# Mainboard_MCU_Breakout.net
KiCad netlist of a schematic drawn in Altium Designer
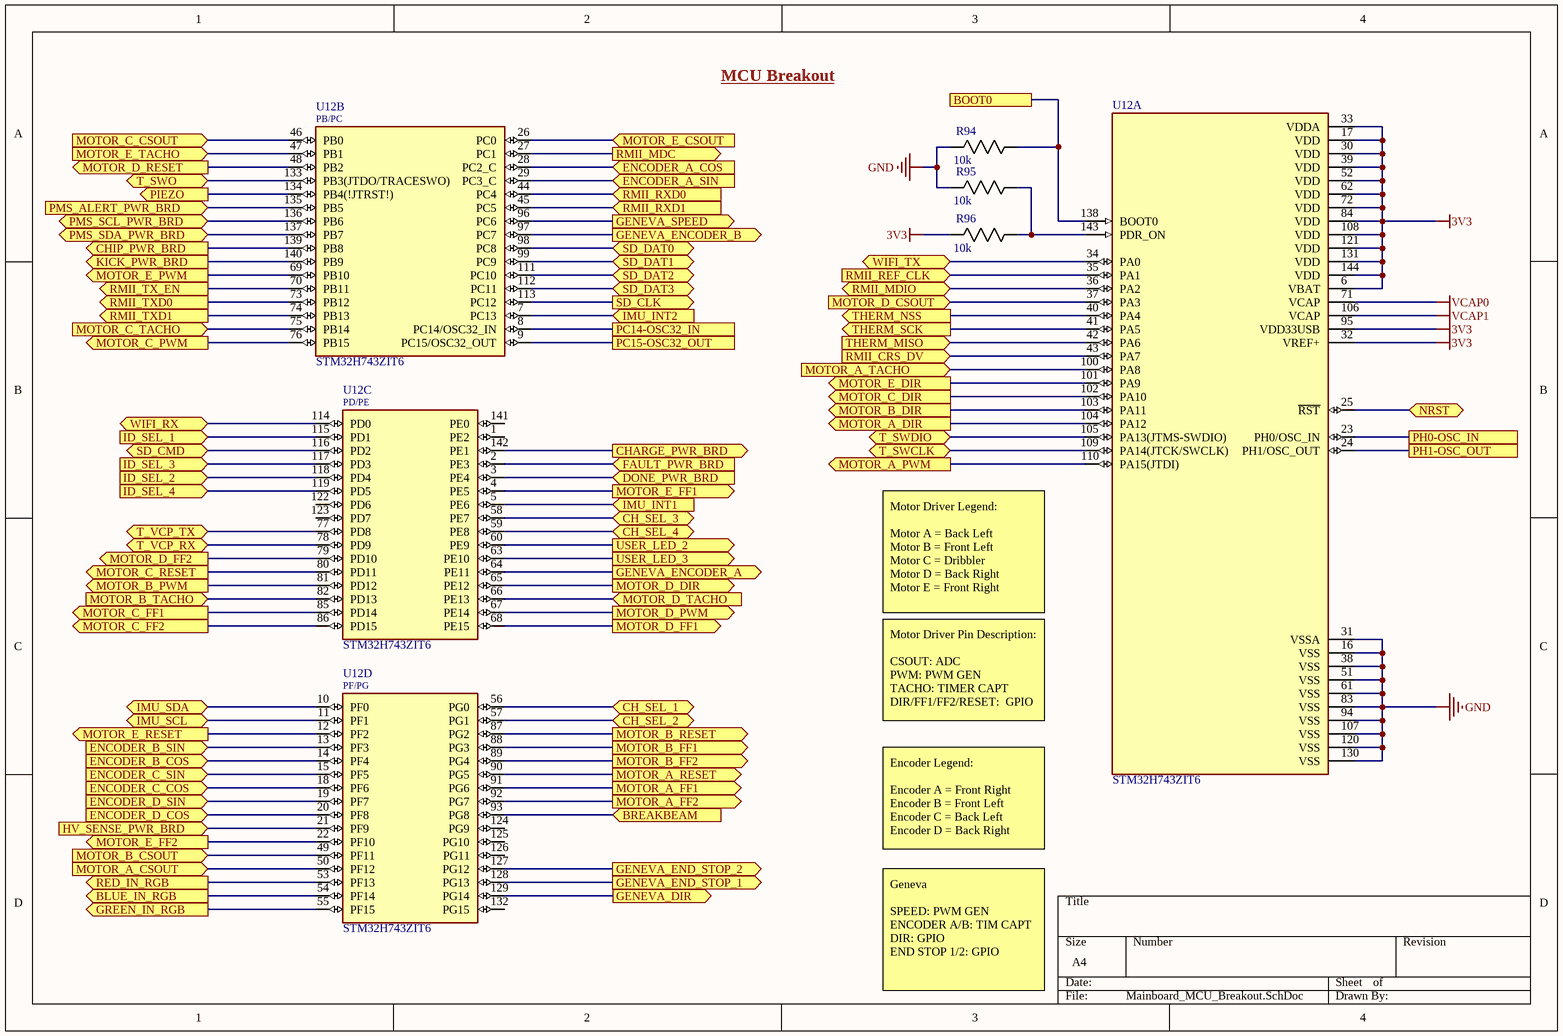
[diagram p0: Mainboard_MCU_Breakout.SchDoc]

(export (version "E")
  (design (tool "Eeschema 10.0.6"))
  (components
    (comp (ref "R94")
      (value "10k")
      (footprint "0805")
      (description "RES SMD 10K OHM 1% 1/8W 0805")
      (fields (field (name "TOLERANCE") "1%"))
      (libsource (lib "") (part "RES 10k 1/8W - 1%_1"))
    )
    (comp (ref "R95")
      (value "10k")
      (footprint "0805")
      (description "RES SMD 10K OHM 1% 1/8W 0805")
      (fields (field (name "TOLERANCE") "1%"))
      (libsource (lib "AltiumLibraries") (part "RES 10k 1/8W - 1%"))
    )
    (comp (ref "R96")
      (value "10k")
      (footprint "0805")
      (description "RES SMD 10K OHM 1% 1/8W 0805")
      (fields (field (name "TOLERANCE") "1%"))
      (libsource (lib "AltiumLibraries") (part "RES 10k 1/8W - 1%"))
    )
    (comp (ref "U12")
      (value "STM32H743ZIT6")
      (footprint "QFP50P2200X2200X160-144N")
      (description "ARM® Cortex®-M7 STM32H7 Microcontroller IC 32-Bit 480MHz 2MB (2M x 8) FLASH 144-LQFP (20x20)")
      (fields (field (name "MF") "STMicroelectronics"))
      (libsource (lib "AltiumLibraries") (part "STM32H743ZIT6"))
    )
  )
  (nets
    (net (code "1") (name "/BLUE_IN_RGB") (class "Default")
      (node (ref "U12") (pin "54") (pinfunction "PF14_54") (pintype "bidirectional"))
    )
    (net (code "2") (name "/BOOT0") (class "Default")
      (node (ref "R94") (pin "1") (pinfunction "R1_1") (pintype "passive"))
      (node (ref "U12") (pin "138") (pinfunction "BOOT0_138") (pintype "input"))
    )
    (net (code "3") (name "/BREAKBEAM") (class "Default")
      (node (ref "U12") (pin "93") (pinfunction "PG8_93") (pintype "bidirectional"))
    )
    (net (code "4") (name "/CHARGE_PWR_BRD") (class "Default")
      (node (ref "U12") (pin "142") (pinfunction "PE1_142") (pintype "bidirectional"))
    )
    (net (code "5") (name "/CHIP_PWR_BRD") (class "Default")
      (node (ref "U12") (pin "139") (pinfunction "PB8_139") (pintype "bidirectional"))
    )
    (net (code "6") (name "/CH_SEL_1") (class "Default")
      (node (ref "U12") (pin "56") (pinfunction "PG0_56") (pintype "bidirectional"))
    )
    (net (code "7") (name "/CH_SEL_2") (class "Default")
      (node (ref "U12") (pin "57") (pinfunction "PG1_57") (pintype "bidirectional"))
    )
    (net (code "8") (name "/CH_SEL_3") (class "Default")
      (node (ref "U12") (pin "58") (pinfunction "PE7_58") (pintype "bidirectional"))
    )
    (net (code "9") (name "/CH_SEL_4") (class "Default")
      (node (ref "U12") (pin "59") (pinfunction "PE8_59") (pintype "bidirectional"))
    )
    (net (code "10") (name "/DONE_PWR_BRD") (class "Default")
      (node (ref "U12") (pin "3") (pinfunction "PE4_3") (pintype "bidirectional"))
    )
    (net (code "11") (name "/ENCODER_A_COS") (class "Default")
      (node (ref "U12") (pin "28") (pinfunction "PC2_C_28") (pintype "bidirectional"))
    )
    (net (code "12") (name "/ENCODER_A_SIN") (class "Default")
      (node (ref "U12") (pin "29") (pinfunction "PC3_C_29") (pintype "bidirectional"))
    )
    (net (code "13") (name "/ENCODER_B_COS") (class "Default")
      (node (ref "U12") (pin "14") (pinfunction "PF4_14") (pintype "bidirectional"))
    )
    (net (code "14") (name "/ENCODER_B_SIN") (class "Default")
      (node (ref "U12") (pin "13") (pinfunction "PF3_13") (pintype "bidirectional"))
    )
    (net (code "15") (name "/ENCODER_C_COS") (class "Default")
      (node (ref "U12") (pin "18") (pinfunction "PF6_18") (pintype "bidirectional"))
    )
    (net (code "16") (name "/ENCODER_C_SIN") (class "Default")
      (node (ref "U12") (pin "15") (pinfunction "PF5_15") (pintype "bidirectional"))
    )
    (net (code "17") (name "/ENCODER_D_COS") (class "Default")
      (node (ref "U12") (pin "20") (pinfunction "PF8_20") (pintype "bidirectional"))
    )
    (net (code "18") (name "/ENCODER_D_SIN") (class "Default")
      (node (ref "U12") (pin "19") (pinfunction "PF7_19") (pintype "bidirectional"))
    )
    (net (code "19") (name "/FAULT_PWR_BRD") (class "Default")
      (node (ref "U12") (pin "2") (pinfunction "PE3_2") (pintype "bidirectional"))
    )
    (net (code "20") (name "/GENEVA_DIR") (class "Default")
      (node (ref "U12") (pin "129") (pinfunction "PG14_129") (pintype "bidirectional"))
    )
    (net (code "21") (name "/GENEVA_ENCODER_A") (class "Default")
      (node (ref "U12") (pin "64") (pinfunction "PE11_64") (pintype "bidirectional"))
    )
    (net (code "22") (name "/GENEVA_ENCODER_B") (class "Default")
      (node (ref "U12") (pin "97") (pinfunction "PC7_97") (pintype "bidirectional"))
    )
    (net (code "23") (name "/GENEVA_END_STOP_1") (class "Default")
      (node (ref "U12") (pin "128") (pinfunction "PG13_128") (pintype "bidirectional"))
    )
    (net (code "24") (name "/GENEVA_END_STOP_2") (class "Default")
      (node (ref "U12") (pin "127") (pinfunction "PG12_127") (pintype "bidirectional"))
    )
    (net (code "25") (name "/GENEVA_SPEED") (class "Default")
      (node (ref "U12") (pin "96") (pinfunction "PC6_96") (pintype "bidirectional"))
    )
    (net (code "26") (name "/GREEN_IN_RGB") (class "Default")
      (node (ref "U12") (pin "55") (pinfunction "PF15_55") (pintype "bidirectional"))
    )
    (net (code "27") (name "/HV_SENSE_PWR_BRD") (class "Default")
      (node (ref "U12") (pin "21") (pinfunction "PF9_21") (pintype "bidirectional"))
    )
    (net (code "28") (name "/ID_SEL_1") (class "Default")
      (node (ref "U12") (pin "115") (pinfunction "PD1_115") (pintype "bidirectional"))
    )
    (net (code "29") (name "/ID_SEL_2") (class "Default")
      (node (ref "U12") (pin "118") (pinfunction "PD4_118") (pintype "bidirectional"))
    )
    (net (code "30") (name "/ID_SEL_3") (class "Default")
      (node (ref "U12") (pin "117") (pinfunction "PD3_117") (pintype "bidirectional"))
    )
    (net (code "31") (name "/ID_SEL_4") (class "Default")
      (node (ref "U12") (pin "119") (pinfunction "PD5_119") (pintype "bidirectional"))
    )
    (net (code "32") (name "/IMU_INT1") (class "Default")
      (node (ref "U12") (pin "5") (pinfunction "PE6_5") (pintype "bidirectional"))
    )
    (net (code "33") (name "/IMU_INT2") (class "Default")
      (node (ref "U12") (pin "7") (pinfunction "PC13_7") (pintype "bidirectional"))
    )
    (net (code "34") (name "/IMU_SCL") (class "Default")
      (node (ref "U12") (pin "11") (pinfunction "PF1_11") (pintype "bidirectional"))
    )
    (net (code "35") (name "/IMU_SDA") (class "Default")
      (node (ref "U12") (pin "10") (pinfunction "PF0_10") (pintype "bidirectional"))
    )
    (net (code "36") (name "/KICK_PWR_BRD") (class "Default")
      (node (ref "U12") (pin "140") (pinfunction "PB9_140") (pintype "bidirectional"))
    )
    (net (code "37") (name "/MOTOR_A_CSOUT") (class "Default")
      (node (ref "U12") (pin "50") (pinfunction "PF12_50") (pintype "bidirectional"))
    )
    (net (code "38") (name "/MOTOR_A_DIR") (class "Default")
      (node (ref "U12") (pin "104") (pinfunction "PA12_104") (pintype "bidirectional"))
    )
    (net (code "39") (name "/MOTOR_A_FF1") (class "Default")
      (node (ref "U12") (pin "91") (pinfunction "PG6_91") (pintype "bidirectional"))
    )
    (net (code "40") (name "/MOTOR_A_FF2") (class "Default")
      (node (ref "U12") (pin "92") (pinfunction "PG7_92") (pintype "bidirectional"))
    )
    (net (code "41") (name "/MOTOR_A_PWM") (class "Default")
      (node (ref "U12") (pin "110") (pinfunction "PA15(JTDI)_110") (pintype "bidirectional"))
    )
    (net (code "42") (name "/MOTOR_A_RESET") (class "Default")
      (node (ref "U12") (pin "90") (pinfunction "PG5_90") (pintype "bidirectional"))
    )
    (net (code "43") (name "/MOTOR_A_TACHO") (class "Default")
      (node (ref "U12") (pin "100") (pinfunction "PA8_100") (pintype "bidirectional"))
    )
    (net (code "44") (name "/MOTOR_B_CSOUT") (class "Default")
      (node (ref "U12") (pin "49") (pinfunction "PF11_49") (pintype "bidirectional"))
    )
    (net (code "45") (name "/MOTOR_B_DIR") (class "Default")
      (node (ref "U12") (pin "103") (pinfunction "PA11_103") (pintype "bidirectional"))
    )
    (net (code "46") (name "/MOTOR_B_FF1") (class "Default")
      (node (ref "U12") (pin "88") (pinfunction "PG3_88") (pintype "bidirectional"))
    )
    (net (code "47") (name "/MOTOR_B_FF2") (class "Default")
      (node (ref "U12") (pin "89") (pinfunction "PG4_89") (pintype "bidirectional"))
    )
    (net (code "48") (name "/MOTOR_B_PWM") (class "Default")
      (node (ref "U12") (pin "81") (pinfunction "PD12_81") (pintype "bidirectional"))
    )
    (net (code "49") (name "/MOTOR_B_RESET") (class "Default")
      (node (ref "U12") (pin "87") (pinfunction "PG2_87") (pintype "bidirectional"))
    )
    (net (code "50") (name "/MOTOR_B_TACHO") (class "Default")
      (node (ref "U12") (pin "82") (pinfunction "PD13_82") (pintype "bidirectional"))
    )
    (net (code "51") (name "/MOTOR_C_CSOUT") (class "Default")
      (node (ref "U12") (pin "46") (pinfunction "PB0_46") (pintype "bidirectional"))
    )
    (net (code "52") (name "/MOTOR_C_DIR") (class "Default")
      (node (ref "U12") (pin "102") (pinfunction "PA10_102") (pintype "bidirectional"))
    )
    (net (code "53") (name "/MOTOR_C_FF1") (class "Default")
      (node (ref "U12") (pin "85") (pinfunction "PD14_85") (pintype "bidirectional"))
    )
    (net (code "54") (name "/MOTOR_C_FF2") (class "Default")
      (node (ref "U12") (pin "86") (pinfunction "PD15_86") (pintype "bidirectional"))
    )
    (net (code "55") (name "/MOTOR_C_PWM") (class "Default")
      (node (ref "U12") (pin "76") (pinfunction "PB15_76") (pintype "bidirectional"))
    )
    (net (code "56") (name "/MOTOR_C_RESET") (class "Default")
      (node (ref "U12") (pin "80") (pinfunction "PD11_80") (pintype "bidirectional"))
    )
    (net (code "57") (name "/MOTOR_C_TACHO") (class "Default")
      (node (ref "U12") (pin "75") (pinfunction "PB14_75") (pintype "bidirectional"))
    )
    (net (code "58") (name "/MOTOR_D_CSOUT") (class "Default")
      (node (ref "U12") (pin "37") (pinfunction "PA3_37") (pintype "bidirectional"))
    )
    (net (code "59") (name "/MOTOR_D_DIR") (class "Default")
      (node (ref "U12") (pin "65") (pinfunction "PE12_65") (pintype "bidirectional"))
    )
    (net (code "60") (name "/MOTOR_D_FF1") (class "Default")
      (node (ref "U12") (pin "68") (pinfunction "PE15_68") (pintype "bidirectional"))
    )
    (net (code "61") (name "/MOTOR_D_FF2") (class "Default")
      (node (ref "U12") (pin "79") (pinfunction "PD10_79") (pintype "bidirectional"))
    )
    (net (code "62") (name "/MOTOR_D_PWM") (class "Default")
      (node (ref "U12") (pin "67") (pinfunction "PE14_67") (pintype "bidirectional"))
    )
    (net (code "63") (name "/MOTOR_D_RESET") (class "Default")
      (node (ref "U12") (pin "48") (pinfunction "PB2_48") (pintype "bidirectional"))
    )
    (net (code "64") (name "/MOTOR_D_TACHO") (class "Default")
      (node (ref "U12") (pin "66") (pinfunction "PE13_66") (pintype "bidirectional"))
    )
    (net (code "65") (name "/MOTOR_E_CSOUT") (class "Default")
      (node (ref "U12") (pin "26") (pinfunction "PC0_26") (pintype "bidirectional"))
    )
    (net (code "66") (name "/MOTOR_E_DIR") (class "Default")
      (node (ref "U12") (pin "101") (pinfunction "PA9_101") (pintype "bidirectional"))
    )
    (net (code "67") (name "/MOTOR_E_FF1") (class "Default")
      (node (ref "U12") (pin "4") (pinfunction "PE5_4") (pintype "bidirectional"))
    )
    (net (code "68") (name "/MOTOR_E_FF2") (class "Default")
      (node (ref "U12") (pin "22") (pinfunction "PF10_22") (pintype "bidirectional"))
    )
    (net (code "69") (name "/MOTOR_E_PWM") (class "Default")
      (node (ref "U12") (pin "69") (pinfunction "PB10_69") (pintype "bidirectional"))
    )
    (net (code "70") (name "/MOTOR_E_RESET") (class "Default")
      (node (ref "U12") (pin "12") (pinfunction "PF2_12") (pintype "bidirectional"))
    )
    (net (code "71") (name "/MOTOR_E_TACHO") (class "Default")
      (node (ref "U12") (pin "47") (pinfunction "PB1_47") (pintype "bidirectional"))
    )
    (net (code "72") (name "/NRST") (class "Default")
      (node (ref "U12") (pin "25") (pinfunction "~{RST}_25") (pintype "bidirectional"))
    )
    (net (code "73") (name "/PC14-OSC32_IN") (class "Default")
      (node (ref "U12") (pin "8") (pinfunction "PC14/OSC32_IN_8") (pintype "bidirectional"))
    )
    (net (code "74") (name "/PC15-OSC32_OUT") (class "Default")
      (node (ref "U12") (pin "9") (pinfunction "PC15/OSC32_OUT_9") (pintype "bidirectional"))
    )
    (net (code "75") (name "/PH0-OSC_IN") (class "Default")
      (node (ref "U12") (pin "23") (pinfunction "PH0/OSC_IN_23") (pintype "bidirectional"))
    )
    (net (code "76") (name "/PH1-OSC_OUT") (class "Default")
      (node (ref "U12") (pin "24") (pinfunction "PH1/OSC_OUT_24") (pintype "bidirectional"))
    )
    (net (code "77") (name "/PIEZO") (class "Default")
      (node (ref "U12") (pin "134") (pinfunction "PB4(!JTRST!)_134") (pintype "bidirectional"))
    )
    (net (code "78") (name "/PMS_ALERT_PWR_BRD") (class "Default")
      (node (ref "U12") (pin "135") (pinfunction "PB5_135") (pintype "bidirectional"))
    )
    (net (code "79") (name "/PMS_SCL_PWR_BRD") (class "Default")
      (node (ref "U12") (pin "136") (pinfunction "PB6_136") (pintype "bidirectional"))
    )
    (net (code "80") (name "/PMS_SDA_PWR_BRD") (class "Default")
      (node (ref "U12") (pin "137") (pinfunction "PB7_137") (pintype "bidirectional"))
    )
    (net (code "81") (name "/RED_IN_RGB") (class "Default")
      (node (ref "U12") (pin "53") (pinfunction "PF13_53") (pintype "bidirectional"))
    )
    (net (code "82") (name "/RMII_CRS_DV") (class "Default")
      (node (ref "U12") (pin "43") (pinfunction "PA7_43") (pintype "bidirectional"))
    )
    (net (code "83") (name "/RMII_MDC") (class "Default")
      (node (ref "U12") (pin "27") (pinfunction "PC1_27") (pintype "bidirectional"))
    )
    (net (code "84") (name "/RMII_MDIO") (class "Default")
      (node (ref "U12") (pin "36") (pinfunction "PA2_36") (pintype "bidirectional"))
    )
    (net (code "85") (name "/RMII_REF_CLK") (class "Default")
      (node (ref "U12") (pin "35") (pinfunction "PA1_35") (pintype "bidirectional"))
    )
    (net (code "86") (name "/RMII_RXD0") (class "Default")
      (node (ref "U12") (pin "44") (pinfunction "PC4_44") (pintype "bidirectional"))
    )
    (net (code "87") (name "/RMII_RXD1") (class "Default")
      (node (ref "U12") (pin "45") (pinfunction "PC5_45") (pintype "bidirectional"))
    )
    (net (code "88") (name "/RMII_TXD0") (class "Default")
      (node (ref "U12") (pin "73") (pinfunction "PB12_73") (pintype "bidirectional"))
    )
    (net (code "89") (name "/RMII_TXD1") (class "Default")
      (node (ref "U12") (pin "74") (pinfunction "PB13_74") (pintype "bidirectional"))
    )
    (net (code "90") (name "/RMII_TX_EN") (class "Default")
      (node (ref "U12") (pin "70") (pinfunction "PB11_70") (pintype "bidirectional"))
    )
    (net (code "91") (name "/SD_CLK") (class "Default")
      (node (ref "U12") (pin "113") (pinfunction "PC12_113") (pintype "bidirectional"))
    )
    (net (code "92") (name "/SD_CMD") (class "Default")
      (node (ref "U12") (pin "116") (pinfunction "PD2_116") (pintype "bidirectional"))
    )
    (net (code "93") (name "/SD_DAT0") (class "Default")
      (node (ref "U12") (pin "98") (pinfunction "PC8_98") (pintype "bidirectional"))
    )
    (net (code "94") (name "/SD_DAT1") (class "Default")
      (node (ref "U12") (pin "99") (pinfunction "PC9_99") (pintype "bidirectional"))
    )
    (net (code "95") (name "/SD_DAT2") (class "Default")
      (node (ref "U12") (pin "111") (pinfunction "PC10_111") (pintype "bidirectional"))
    )
    (net (code "96") (name "/SD_DAT3") (class "Default")
      (node (ref "U12") (pin "112") (pinfunction "PC11_112") (pintype "bidirectional"))
    )
    (net (code "97") (name "/THERM_MISO") (class "Default")
      (node (ref "U12") (pin "42") (pinfunction "PA6_42") (pintype "bidirectional"))
    )
    (net (code "98") (name "/THERM_NSS") (class "Default")
      (node (ref "U12") (pin "40") (pinfunction "PA4_40") (pintype "bidirectional"))
    )
    (net (code "99") (name "/THERM_SCK") (class "Default")
      (node (ref "U12") (pin "41") (pinfunction "PA5_41") (pintype "bidirectional"))
    )
    (net (code "100") (name "/T_SWCLK") (class "Default")
      (node (ref "U12") (pin "109") (pinfunction "PA14(JTCK/SWCLK)_109") (pintype "bidirectional"))
    )
    (net (code "101") (name "/T_SWDIO") (class "Default")
      (node (ref "U12") (pin "105") (pinfunction "PA13(JTMS-SWDIO)_105") (pintype "bidirectional"))
    )
    (net (code "102") (name "/T_SWO") (class "Default")
      (node (ref "U12") (pin "133") (pinfunction "PB3(JTDO/TRACESWO)_133") (pintype "bidirectional"))
    )
    (net (code "103") (name "/T_VCP_RX") (class "Default")
      (node (ref "U12") (pin "78") (pinfunction "PD9_78") (pintype "bidirectional"))
    )
    (net (code "104") (name "/T_VCP_TX") (class "Default")
      (node (ref "U12") (pin "77") (pinfunction "PD8_77") (pintype "bidirectional"))
    )
    (net (code "105") (name "/USER_LED_2") (class "Default")
      (node (ref "U12") (pin "60") (pinfunction "PE9_60") (pintype "bidirectional"))
    )
    (net (code "106") (name "/USER_LED_3") (class "Default")
      (node (ref "U12") (pin "63") (pinfunction "PE10_63") (pintype "bidirectional"))
    )
    (net (code "107") (name "/WIFI_RX") (class "Default")
      (node (ref "U12") (pin "114") (pinfunction "PD0_114") (pintype "bidirectional"))
    )
    (net (code "108") (name "/WIFI_TX") (class "Default")
      (node (ref "U12") (pin "34") (pinfunction "PA0_34") (pintype "bidirectional"))
    )
    (net (code "109") (name "3V3") (class "Default")
      (node (ref "R96") (pin "2") (pinfunction "R2_2") (pintype "passive"))
      (node (ref "U12") (pin "108") (pinfunction "VDD_108") (pintype "power_in"))
      (node (ref "U12") (pin "121") (pinfunction "VDD_121") (pintype "power_in"))
      (node (ref "U12") (pin "131") (pinfunction "VDD_131") (pintype "power_in"))
      (node (ref "U12") (pin "144") (pinfunction "VDD_144") (pintype "power_in"))
      (node (ref "U12") (pin "17") (pinfunction "VDD_17") (pintype "power_in"))
      (node (ref "U12") (pin "30") (pinfunction "VDD_30") (pintype "power_in"))
      (node (ref "U12") (pin "32") (pinfunction "VREF+_32") (pintype "power_in"))
      (node (ref "U12") (pin "33") (pinfunction "VDDA_33") (pintype "power_in"))
      (node (ref "U12") (pin "39") (pinfunction "VDD_39") (pintype "power_in"))
      (node (ref "U12") (pin "52") (pinfunction "VDD_52") (pintype "power_in"))
      (node (ref "U12") (pin "6") (pinfunction "VBAT_6") (pintype "power_in"))
      (node (ref "U12") (pin "62") (pinfunction "VDD_62") (pintype "power_in"))
      (node (ref "U12") (pin "72") (pinfunction "VDD_72") (pintype "power_in"))
      (node (ref "U12") (pin "84") (pinfunction "VDD_84") (pintype "power_in"))
      (node (ref "U12") (pin "95") (pinfunction "VDD33USB_95") (pintype "power_in"))
    )
    (net (code "110") (name "GND") (class "Default")
      (node (ref "R94") (pin "2") (pinfunction "R2_2") (pintype "passive"))
      (node (ref "R95") (pin "2") (pinfunction "R2_2") (pintype "passive"))
      (node (ref "U12") (pin "107") (pinfunction "VSS_107") (pintype "power_in"))
      (node (ref "U12") (pin "120") (pinfunction "VSS_120") (pintype "power_in"))
      (node (ref "U12") (pin "130") (pinfunction "VSS_130") (pintype "power_in"))
      (node (ref "U12") (pin "16") (pinfunction "VSS_16") (pintype "power_in"))
      (node (ref "U12") (pin "31") (pinfunction "VSSA_31") (pintype "power_in"))
      (node (ref "U12") (pin "38") (pinfunction "VSS_38") (pintype "power_in"))
      (node (ref "U12") (pin "51") (pinfunction "VSS_51") (pintype "power_in"))
      (node (ref "U12") (pin "61") (pinfunction "VSS_61") (pintype "power_in"))
      (node (ref "U12") (pin "83") (pinfunction "VSS_83") (pintype "power_in"))
      (node (ref "U12") (pin "94") (pinfunction "VSS_94") (pintype "power_in"))
    )
    (net (code "111") (name "Net-(R95-R1)") (class "Default")
      (node (ref "R95") (pin "1") (pinfunction "R1_1") (pintype "passive"))
      (node (ref "R96") (pin "1") (pinfunction "R1_1") (pintype "passive"))
      (node (ref "U12") (pin "143") (pinfunction "PDR_ON_143") (pintype "input"))
    )
    (net (code "112") (name "VCAP0") (class "Default")
      (node (ref "U12") (pin "71") (pinfunction "VCAP_71") (pintype "power_in"))
    )
    (net (code "113") (name "VCAP1") (class "Default")
      (node (ref "U12") (pin "106") (pinfunction "VCAP_106") (pintype "power_in"))
    )
    (net (code "114") (name "unconnected-(U12C-PD6-Pad122)") (class "Default")
      (node (ref "U12") (pin "122") (pinfunction "PD6_122") (pintype "bidirectional"))
    )
    (net (code "115") (name "unconnected-(U12C-PD7-Pad123)") (class "Default")
      (node (ref "U12") (pin "123") (pinfunction "PD7_123") (pintype "bidirectional"))
    )
    (net (code "116") (name "unconnected-(U12C-PE0-Pad141)") (class "Default")
      (node (ref "U12") (pin "141") (pinfunction "PE0_141") (pintype "bidirectional"))
    )
    (net (code "117") (name "unconnected-(U12C-PE2-Pad1)") (class "Default")
      (node (ref "U12") (pin "1") (pinfunction "PE2_1") (pintype "bidirectional"))
    )
    (net (code "118") (name "unconnected-(U12D-PG9-Pad124)") (class "Default")
      (node (ref "U12") (pin "124") (pinfunction "PG9_124") (pintype "bidirectional"))
    )
    (net (code "119") (name "unconnected-(U12D-PG10-Pad125)") (class "Default")
      (node (ref "U12") (pin "125") (pinfunction "PG10_125") (pintype "bidirectional"))
    )
    (net (code "120") (name "unconnected-(U12D-PG11-Pad126)") (class "Default")
      (node (ref "U12") (pin "126") (pinfunction "PG11_126") (pintype "bidirectional"))
    )
    (net (code "121") (name "unconnected-(U12D-PG15-Pad132)") (class "Default")
      (node (ref "U12") (pin "132") (pinfunction "PG15_132") (pintype "bidirectional"))
    )
  )
)
